# Artefato2Esquema.net
KiCad netlist of a schematic drawn in EasyEDA
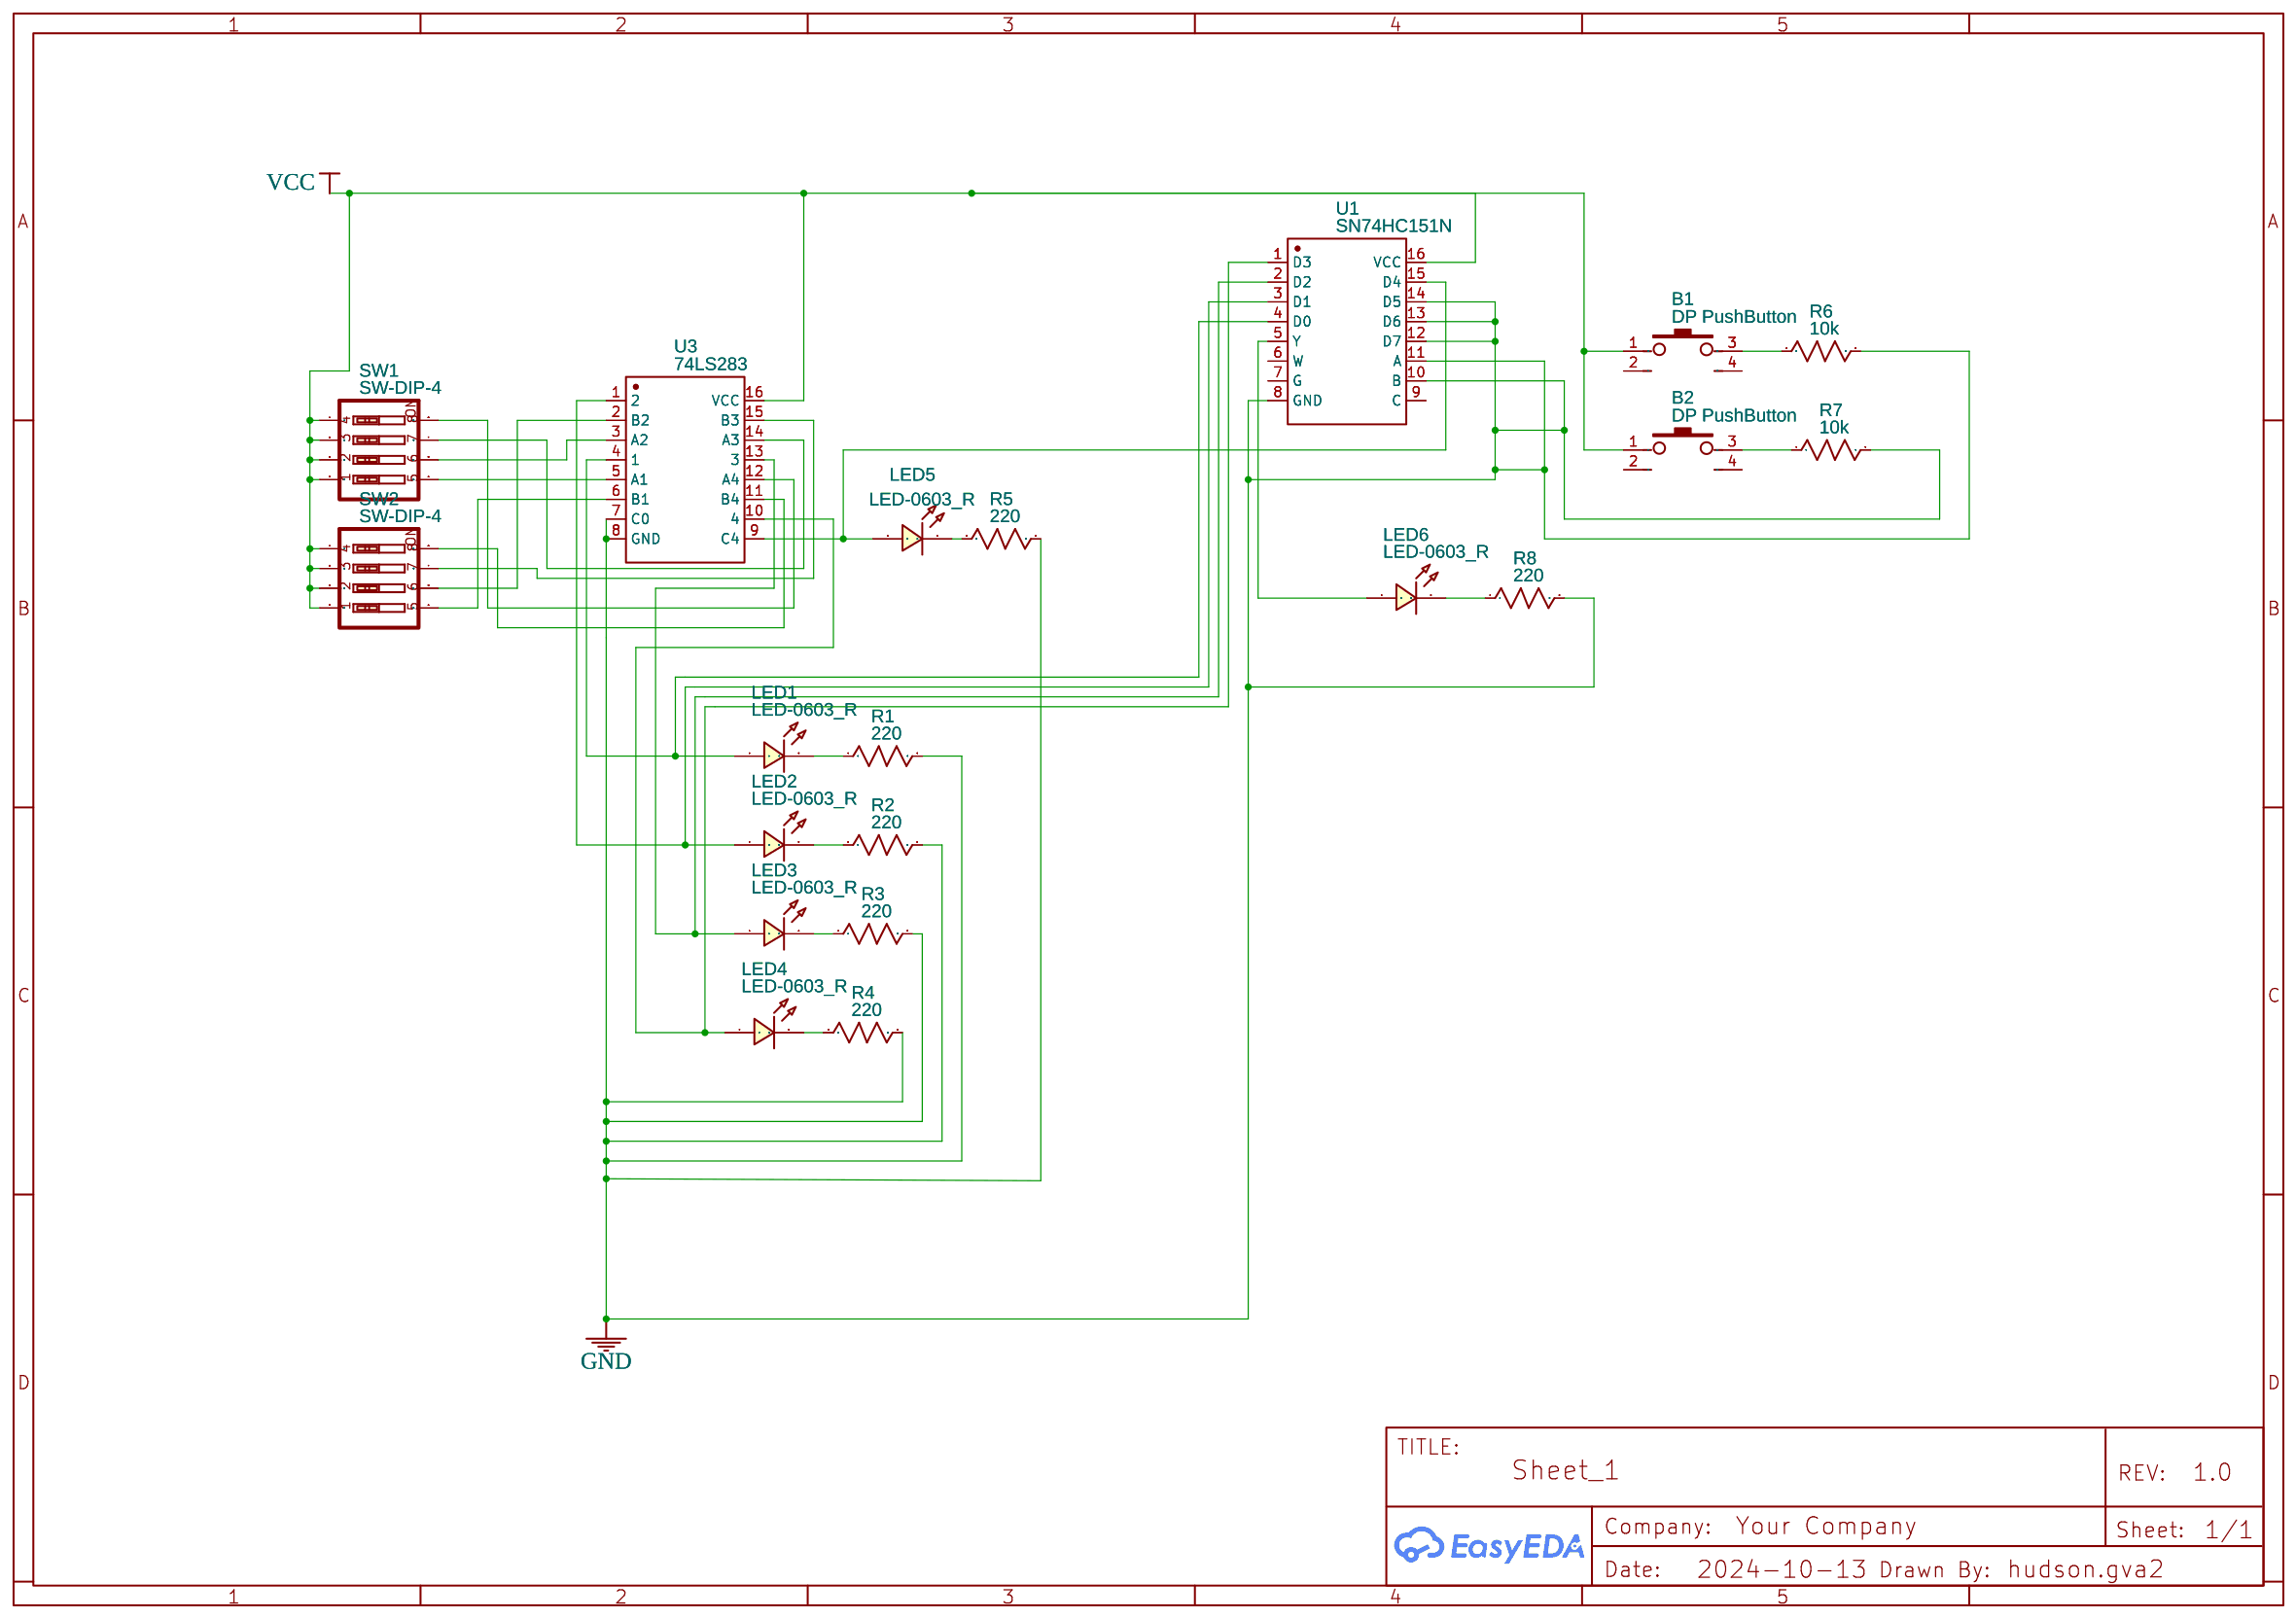
[diagram p0: schematic sheet]

(export (version "E")
  (design (tool "Eeschema 10.0.6"))
  (components
    (comp (ref "B1")
      (value "DP PushButton")
      (fields (field (name "Manufacturer Part") "New SchematicLib"))
      (libsource (lib "") (part "DP PushButton"))
    )
    (comp (ref "B2")
      (value "DP PushButton")
      (fields (field (name "Manufacturer Part") "New SchematicLib"))
      (libsource (lib "") (part "DP PushButton"))
    )
    (comp (ref "LED1")
      (value "LED-0603_R")
      (fields
        (field (name "Manufacturer Part") "19-217/R6C-AL1M2VY/3T")
        (field (name "Manufacturer") "EVERLIGHT(台湾亿光)")
      )
      (libsource (lib "") (part "LED-0603_R"))
    )
    (comp (ref "LED2")
      (value "LED-0603_R")
      (fields
        (field (name "Manufacturer Part") "19-217/R6C-AL1M2VY/3T")
        (field (name "Manufacturer") "EVERLIGHT(台湾亿光)")
      )
      (libsource (lib "") (part "LED-0603_R"))
    )
    (comp (ref "LED3")
      (value "LED-0603_R")
      (fields
        (field (name "Manufacturer Part") "19-217/R6C-AL1M2VY/3T")
        (field (name "Manufacturer") "EVERLIGHT(台湾亿光)")
      )
      (libsource (lib "") (part "LED-0603_R"))
    )
    (comp (ref "LED4")
      (value "LED-0603_R")
      (fields
        (field (name "Manufacturer Part") "19-217/R6C-AL1M2VY/3T")
        (field (name "Manufacturer") "EVERLIGHT(台湾亿光)")
      )
      (libsource (lib "") (part "LED-0603_R"))
    )
    (comp (ref "LED5")
      (value "LED-0603_R")
      (fields
        (field (name "Manufacturer Part") "19-217/R6C-AL1M2VY/3T")
        (field (name "Manufacturer") "EVERLIGHT(台湾亿光)")
      )
      (libsource (lib "") (part "LED-0603_R"))
    )
    (comp (ref "LED6")
      (value "LED-0603_R")
      (fields
        (field (name "Manufacturer Part") "19-217/R6C-AL1M2VY/3T")
        (field (name "Manufacturer") "EVERLIGHT(台湾亿光)")
      )
      (libsource (lib "") (part "LED-0603_R"))
    )
    (comp (ref "R1") (value "220") (libsource (lib "") (part "R_0603_US")))
    (comp (ref "R2") (value "220") (libsource (lib "") (part "R_0603_US")))
    (comp (ref "R3") (value "220") (libsource (lib "") (part "R_0603_US")))
    (comp (ref "R4") (value "220") (libsource (lib "") (part "R_0603_US")))
    (comp (ref "R5") (value "220") (libsource (lib "") (part "R_0603_US")))
    (comp (ref "R6") (value "10k") (libsource (lib "") (part "R_0603_US")))
    (comp (ref "R7") (value "10k") (libsource (lib "") (part "R_0603_US")))
    (comp (ref "R8") (value "220") (libsource (lib "") (part "R_0603_US")))
    (comp (ref "SW1") (value "SW-DIP-4") (libsource (lib "") (part "SW-DIP-4")))
    (comp (ref "SW2") (value "SW-DIP-4") (libsource (lib "") (part "SW-DIP-4")))
    (comp (ref "U1") (value "SN74HC151N") (libsource (lib "") (part "SN74HC151N")))
    (comp (ref "U3")
      (value "74LS283")
      (fields (field (name "Manufacturer Part") "SN74LS283D") (field (name "Manufacturer") "TI(德州仪器)"))
      (libsource (lib "") (part "74LS283"))
    )
  )
  (nets
    (net (code "1") (name "GND") (class "Default")
      (node (ref "R1") (pin "2") (pinfunction "2_2") (pintype "unspecified"))
      (node (ref "R2") (pin "2") (pinfunction "2_2") (pintype "unspecified"))
      (node (ref "R3") (pin "2") (pinfunction "2_2") (pintype "unspecified"))
      (node (ref "R4") (pin "2") (pinfunction "2_2") (pintype "unspecified"))
      (node (ref "R5") (pin "2") (pinfunction "2_2") (pintype "unspecified"))
      (node (ref "R6") (pin "2") (pinfunction "2_2") (pintype "unspecified"))
      (node (ref "R7") (pin "2") (pinfunction "2_2") (pintype "unspecified"))
      (node (ref "R8") (pin "2") (pinfunction "2_2") (pintype "unspecified"))
      (node (ref "U1") (pin "10") (pinfunction "B_10") (pintype "unspecified"))
      (node (ref "U1") (pin "11") (pinfunction "A_11") (pintype "unspecified"))
      (node (ref "U1") (pin "12") (pinfunction "D7_12") (pintype "unspecified"))
      (node (ref "U1") (pin "13") (pinfunction "D6_13") (pintype "unspecified"))
      (node (ref "U1") (pin "14") (pinfunction "D5_14") (pintype "unspecified"))
      (node (ref "U1") (pin "8") (pinfunction "GND_8") (pintype "unspecified"))
      (node (ref "U3") (pin "7") (pinfunction "C0_7") (pintype "unspecified"))
      (node (ref "U3") (pin "8") (pinfunction "GND_8") (pintype "unspecified"))
    )
    (net (code "2") (name "Net-(B1-Pad3)") (class "Default")
      (node (ref "B1") (pin "3") (pinfunction "3_3") (pintype "input"))
      (node (ref "R6") (pin "1") (pinfunction "1_1") (pintype "unspecified"))
    )
    (net (code "3") (name "Net-(B2-Pad3)") (class "Default")
      (node (ref "B2") (pin "3") (pinfunction "3_3") (pintype "input"))
      (node (ref "R7") (pin "1") (pinfunction "1_1") (pintype "unspecified"))
    )
    (net (code "4") (name "Net-(LED1-Pad2)") (class "Default")
      (node (ref "LED1") (pin "2") (pinfunction "2_2") (pintype "unspecified"))
      (node (ref "R1") (pin "1") (pinfunction "1_1") (pintype "unspecified"))
    )
    (net (code "5") (name "Net-(LED2-Pad2)") (class "Default")
      (node (ref "LED2") (pin "2") (pinfunction "2_2") (pintype "unspecified"))
      (node (ref "R2") (pin "1") (pinfunction "1_1") (pintype "unspecified"))
    )
    (net (code "6") (name "Net-(LED3-Pad2)") (class "Default")
      (node (ref "LED3") (pin "2") (pinfunction "2_2") (pintype "unspecified"))
      (node (ref "R3") (pin "1") (pinfunction "1_1") (pintype "unspecified"))
    )
    (net (code "7") (name "Net-(LED4-Pad2)") (class "Default")
      (node (ref "LED4") (pin "2") (pinfunction "2_2") (pintype "unspecified"))
      (node (ref "R4") (pin "1") (pinfunction "1_1") (pintype "unspecified"))
    )
    (net (code "8") (name "Net-(LED5-Pad2)") (class "Default")
      (node (ref "LED5") (pin "2") (pinfunction "2_2") (pintype "unspecified"))
      (node (ref "R5") (pin "1") (pinfunction "1_1") (pintype "unspecified"))
    )
    (net (code "9") (name "Net-(LED6-Pad2)") (class "Default")
      (node (ref "LED6") (pin "2") (pinfunction "2_2") (pintype "unspecified"))
      (node (ref "R8") (pin "1") (pinfunction "1_1") (pintype "unspecified"))
    )
    (net (code "10") (name "Net-(SW1-13)") (class "Default")
      (node (ref "SW1") (pin "5") (pinfunction "13_5") (pintype "unspecified"))
      (node (ref "U3") (pin "5") (pinfunction "A1_5") (pintype "unspecified"))
    )
    (net (code "11") (name "Net-(SW1-14)") (class "Default")
      (node (ref "SW1") (pin "6") (pinfunction "14_6") (pintype "unspecified"))
      (node (ref "U3") (pin "3") (pinfunction "A2_3") (pintype "unspecified"))
    )
    (net (code "12") (name "Net-(SW1-15)") (class "Default")
      (node (ref "SW1") (pin "7") (pinfunction "15_7") (pintype "unspecified"))
      (node (ref "U3") (pin "14") (pinfunction "A3_14") (pintype "unspecified"))
    )
    (net (code "13") (name "Net-(SW1-16)") (class "Default")
      (node (ref "SW1") (pin "8") (pinfunction "16_8") (pintype "unspecified"))
      (node (ref "U3") (pin "12") (pinfunction "A4_12") (pintype "unspecified"))
    )
    (net (code "14") (name "Net-(SW2-13)") (class "Default")
      (node (ref "SW2") (pin "5") (pinfunction "13_5") (pintype "unspecified"))
      (node (ref "U3") (pin "6") (pinfunction "B1_6") (pintype "unspecified"))
    )
    (net (code "15") (name "Net-(SW2-14)") (class "Default")
      (node (ref "SW2") (pin "6") (pinfunction "14_6") (pintype "unspecified"))
      (node (ref "U3") (pin "2") (pinfunction "B2_2") (pintype "unspecified"))
    )
    (net (code "16") (name "Net-(SW2-15)") (class "Default")
      (node (ref "SW2") (pin "7") (pinfunction "15_7") (pintype "unspecified"))
      (node (ref "U3") (pin "15") (pinfunction "B3_15") (pintype "unspecified"))
    )
    (net (code "17") (name "Net-(SW2-16)") (class "Default")
      (node (ref "SW2") (pin "8") (pinfunction "16_8") (pintype "unspecified"))
      (node (ref "U3") (pin "11") (pinfunction "B4_11") (pintype "unspecified"))
    )
    (net (code "18") (name "Net-(U1-D0)") (class "Default")
      (node (ref "LED1") (pin "1") (pinfunction "1_1") (pintype "unspecified"))
      (node (ref "U1") (pin "4") (pinfunction "D0_4") (pintype "unspecified"))
      (node (ref "U3") (pin "4") (pinfunction "1_4") (pintype "unspecified"))
    )
    (net (code "19") (name "Net-(U1-D1)") (class "Default")
      (node (ref "LED2") (pin "1") (pinfunction "1_1") (pintype "unspecified"))
      (node (ref "U1") (pin "3") (pinfunction "D1_3") (pintype "unspecified"))
      (node (ref "U3") (pin "1") (pinfunction "2_1") (pintype "unspecified"))
    )
    (net (code "20") (name "Net-(U1-D2)") (class "Default")
      (node (ref "LED3") (pin "1") (pinfunction "1_1") (pintype "unspecified"))
      (node (ref "U1") (pin "2") (pinfunction "D2_2") (pintype "unspecified"))
      (node (ref "U3") (pin "13") (pinfunction "3_13") (pintype "unspecified"))
    )
    (net (code "21") (name "Net-(U1-D3)") (class "Default")
      (node (ref "LED4") (pin "1") (pinfunction "1_1") (pintype "unspecified"))
      (node (ref "U1") (pin "1") (pinfunction "D3_1") (pintype "unspecified"))
      (node (ref "U3") (pin "10") (pinfunction "4_10") (pintype "unspecified"))
    )
    (net (code "22") (name "Net-(U1-D4)") (class "Default")
      (node (ref "LED5") (pin "1") (pinfunction "1_1") (pintype "unspecified"))
      (node (ref "U1") (pin "15") (pinfunction "D4_15") (pintype "unspecified"))
      (node (ref "U3") (pin "9") (pinfunction "C4_9") (pintype "unspecified"))
    )
    (net (code "23") (name "Net-(U1-Y)") (class "Default")
      (node (ref "LED6") (pin "1") (pinfunction "1_1") (pintype "unspecified"))
      (node (ref "U1") (pin "5") (pinfunction "Y_5") (pintype "unspecified"))
    )
    (net (code "24") (name "VCC") (class "Default")
      (node (ref "B1") (pin "1") (pinfunction "1_1") (pintype "input"))
      (node (ref "B2") (pin "1") (pinfunction "1_1") (pintype "input"))
      (node (ref "SW1") (pin "1") (pinfunction "1_1") (pintype "unspecified"))
      (node (ref "SW1") (pin "2") (pinfunction "2_2") (pintype "unspecified"))
      (node (ref "SW1") (pin "3") (pinfunction "3_3") (pintype "unspecified"))
      (node (ref "SW1") (pin "4") (pinfunction "4_4") (pintype "unspecified"))
      (node (ref "SW2") (pin "1") (pinfunction "1_1") (pintype "unspecified"))
      (node (ref "SW2") (pin "2") (pinfunction "2_2") (pintype "unspecified"))
      (node (ref "SW2") (pin "3") (pinfunction "3_3") (pintype "unspecified"))
      (node (ref "SW2") (pin "4") (pinfunction "4_4") (pintype "unspecified"))
      (node (ref "U1") (pin "16") (pinfunction "VCC_16") (pintype "unspecified"))
      (node (ref "U3") (pin "16") (pinfunction "VCC_16") (pintype "unspecified"))
    )
    (net (code "25") (name "unconnected-(B1-1-Pad2)") (class "Default")
      (node (ref "B1") (pin "2") (pinfunction "1_2") (pintype "input"))
    )
    (net (code "26") (name "unconnected-(B1-2-Pad4)") (class "Default")
      (node (ref "B1") (pin "4") (pinfunction "2_4") (pintype "input"))
    )
    (net (code "27") (name "unconnected-(B2-1-Pad2)") (class "Default")
      (node (ref "B2") (pin "2") (pinfunction "1_2") (pintype "input"))
    )
    (net (code "28") (name "unconnected-(B2-2-Pad4)") (class "Default")
      (node (ref "B2") (pin "4") (pinfunction "2_4") (pintype "input"))
    )
    (net (code "29") (name "unconnected-(U1-C-Pad9)") (class "Default")
      (node (ref "U1") (pin "9") (pinfunction "C_9") (pintype "unspecified"))
    )
    (net (code "30") (name "unconnected-(U1-G-Pad7)") (class "Default")
      (node (ref "U1") (pin "7") (pinfunction "G_7") (pintype "unspecified"))
    )
    (net (code "31") (name "unconnected-(U1-W-Pad6)") (class "Default")
      (node (ref "U1") (pin "6") (pinfunction "W_6") (pintype "unspecified"))
    )
  )
)
